# PCB_iter_3.net
KiCad netlist of a schematic drawn in EAGLE
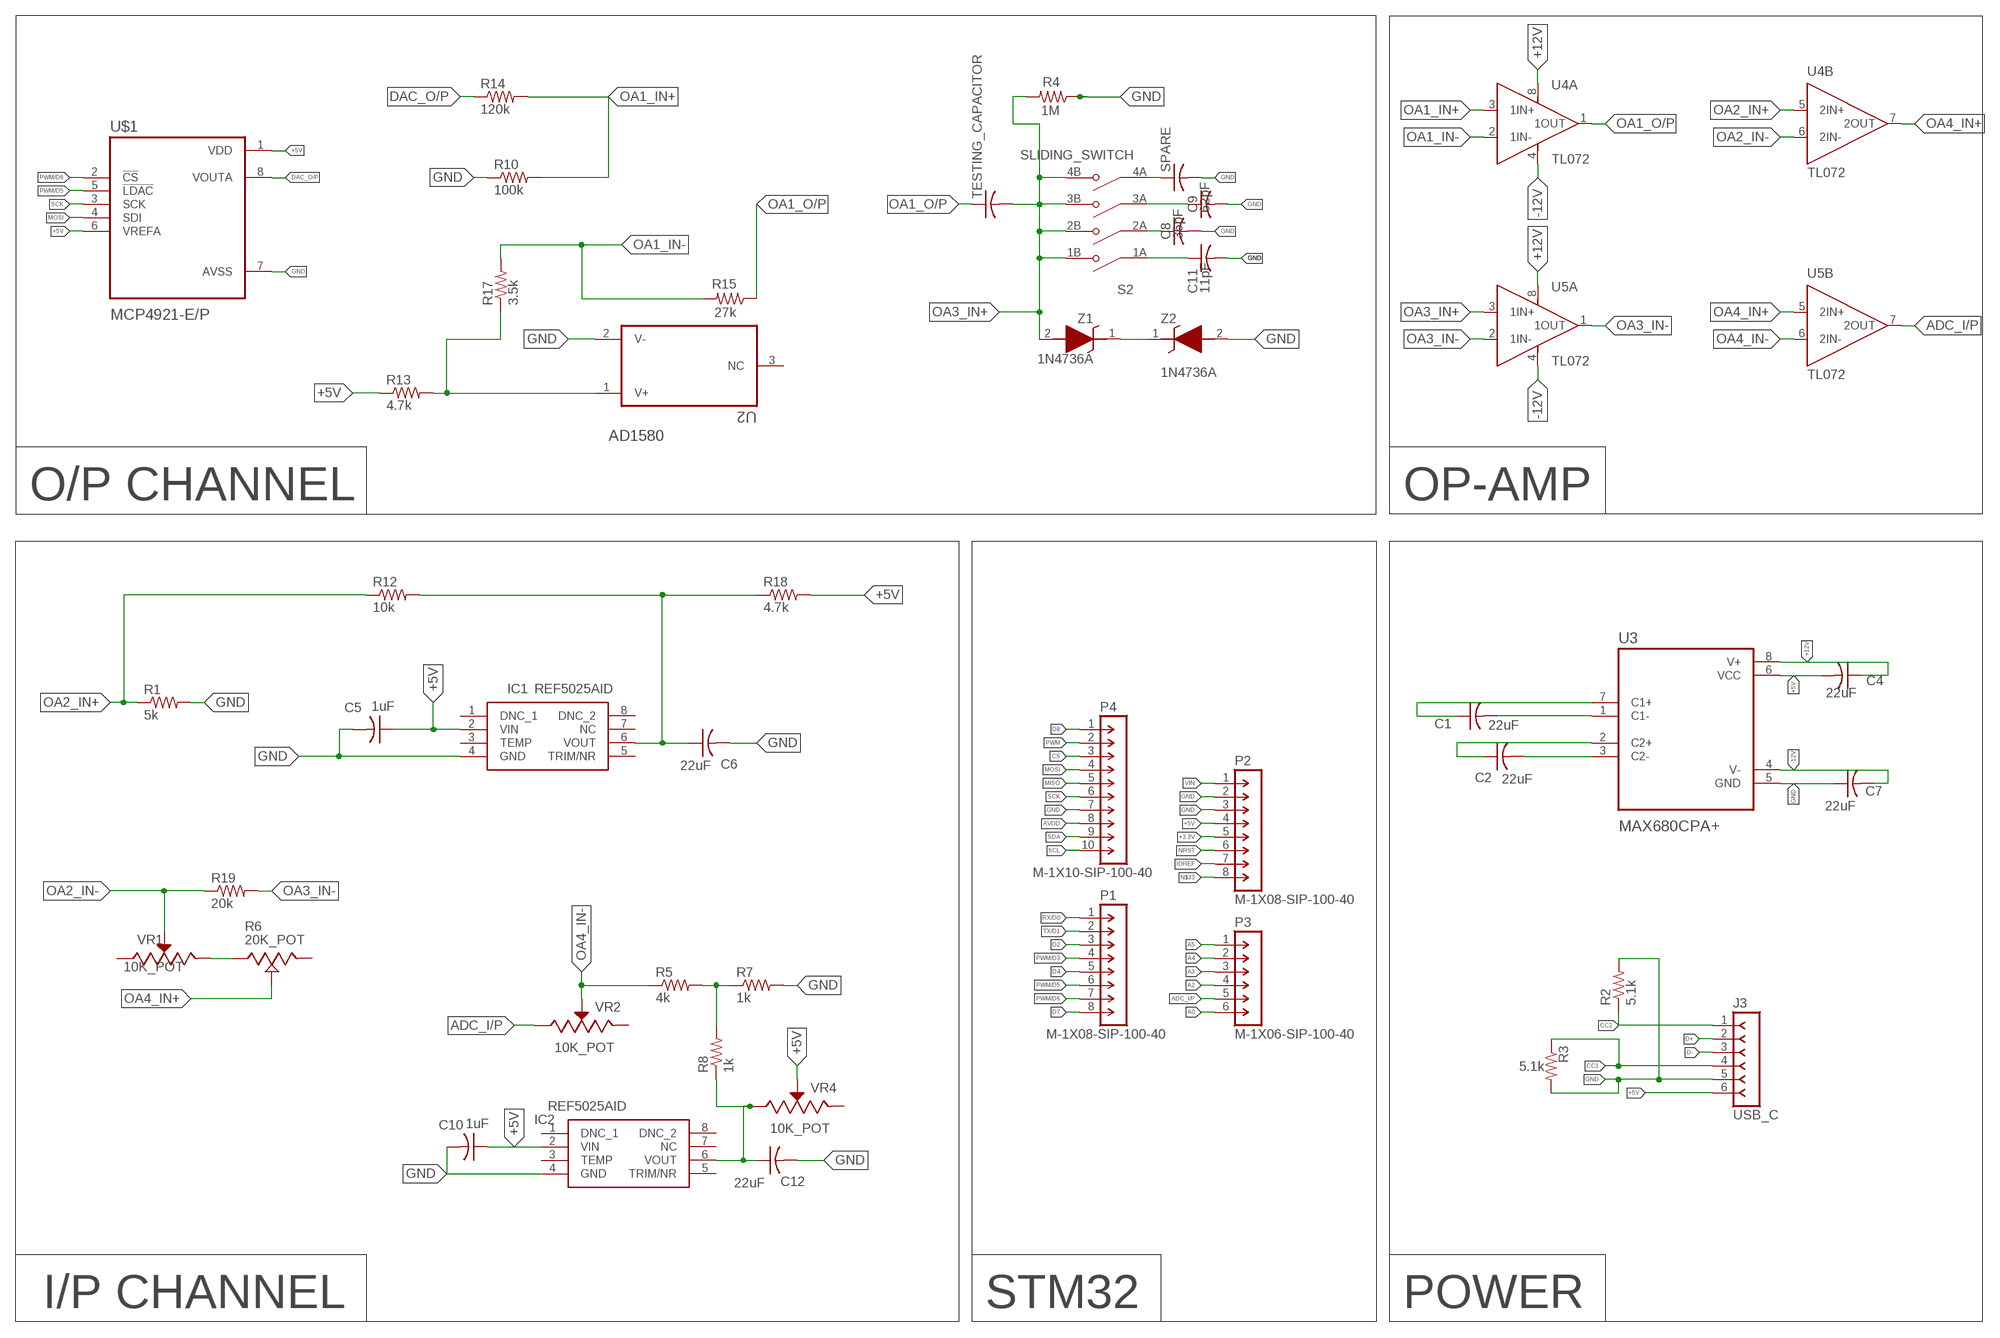
[diagram p0: schematic, sheet 1]

(export (version "E")
  (design (tool "Eeschema 10.0.6"))
  (components
    (comp (ref "C1")
      (value "22uF")
      (footprint "eagle-import:C1206")
      (libsource (lib "eagle-import") (part "C-USC1206"))
    )
    (comp (ref "C2")
      (value "22uF")
      (footprint "eagle-import:C1206")
      (libsource (lib "eagle-import") (part "C-USC1206"))
    )
    (comp (ref "C4")
      (value "22uF")
      (footprint "eagle-import:C1206")
      (libsource (lib "eagle-import") (part "C-USC1206"))
    )
    (comp (ref "C5")
      (value "1uF")
      (footprint "eagle-import:C1206")
      (libsource (lib "eagle-import") (part "C-USC1206"))
    )
    (comp (ref "C6")
      (value "22uF")
      (footprint "eagle-import:C1206")
      (libsource (lib "eagle-import") (part "C-USC1206"))
    )
    (comp (ref "C7")
      (value "22uF")
      (footprint "eagle-import:C1206")
      (libsource (lib "eagle-import") (part "C-USC1206"))
    )
    (comp (ref "C8")
      (value "36pF")
      (footprint "eagle-import:C1206")
      (libsource (lib "eagle-import") (part "C-USC1206"))
    )
    (comp (ref "C9")
      (value "62pF")
      (footprint "eagle-import:C1206")
      (libsource (lib "eagle-import") (part "C-USC1206"))
    )
    (comp (ref "C10")
      (value "1uF")
      (footprint "eagle-import:C1206")
      (libsource (lib "eagle-import") (part "C-USC1206"))
    )
    (comp (ref "C11")
      (value "11pF")
      (footprint "eagle-import:C1206")
      (fields (field (name "SPICEPREFIX") "C"))
      (libsource (lib "eagle-import") (part "C-USC1206"))
    )
    (comp (ref "C12")
      (value "22uF")
      (footprint "eagle-import:C1206")
      (libsource (lib "eagle-import") (part "C-USC1206"))
    )
    (comp (ref "IC1")
      (value "REF5025AID")
      (footprint "eagle-import:SOIC127P600X175-8N")
      (fields (field (name "MOUSER_PART_NUMBER") "595-REF5025AID"))
      (libsource (lib "eagle-import") (part "REF5025AID"))
    )
    (comp (ref "IC2")
      (value "REF5025AID")
      (footprint "eagle-import:SOIC127P600X175-8N")
      (fields (field (name "MOUSER_PART_NUMBER") "595-REF5025AID"))
      (libsource (lib "eagle-import") (part "REF5025AID"))
    )
    (comp (ref "J3")
      (value "USB_C")
      (footprint "eagle-import:SIP-100-06-40Y")
      (libsource (lib "eagle-import") (part "F-1X06-SIP-100-40Y"))
    )
    (comp (ref "P1")
      (value "M-1X08-SIP-100-40")
      (footprint "eagle-import:SIP-100-08-40")
      (libsource (lib "eagle-import") (part "M-1X08-SIP-100-40"))
    )
    (comp (ref "P2")
      (value "M-1X08-SIP-100-40")
      (footprint "eagle-import:SIP-100-08-40")
      (libsource (lib "eagle-import") (part "M-1X08-SIP-100-40"))
    )
    (comp (ref "P3")
      (value "M-1X06-SIP-100-40")
      (footprint "eagle-import:SIP-100-06-40")
      (libsource (lib "eagle-import") (part "M-1X06-SIP-100-40"))
    )
    (comp (ref "P4")
      (value "M-1X10-SIP-100-40")
      (footprint "eagle-import:SIP-100-10-40")
      (libsource (lib "eagle-import") (part "M-1X10-SIP-100-40"))
    )
    (comp (ref "R1")
      (value "5k")
      (footprint "eagle-import:M1206")
      (libsource (lib "eagle-import") (part "R-US_M1206"))
    )
    (comp (ref "R2")
      (value "5.1k")
      (footprint "eagle-import:R1206")
      (libsource (lib "eagle-import") (part "R-US_R1206"))
    )
    (comp (ref "R3")
      (value "5.1k")
      (footprint "eagle-import:R1206")
      (libsource (lib "eagle-import") (part "R-US_R1206"))
    )
    (comp (ref "R4")
      (value "1M")
      (footprint "eagle-import:M1206")
      (libsource (lib "eagle-import") (part "R-US_M1206"))
    )
    (comp (ref "R5")
      (value "4k")
      (footprint "eagle-import:M1206")
      (libsource (lib "eagle-import") (part "R-US_M1206"))
    )
    (comp (ref "R6")
      (value "20K_POT")
      (footprint "eagle-import:TRIM_3296X-1-203LF")
      (fields (field (name "MF") "Bourns") (field (name "MP") "3296X-1-203LF"))
      (libsource (lib "eagle-import") (part "3296X-1-203LF"))
    )
    (comp (ref "R7")
      (value "1k")
      (footprint "eagle-import:M1206")
      (libsource (lib "eagle-import") (part "R-US_M1206"))
    )
    (comp (ref "R8")
      (value "1k")
      (footprint "eagle-import:M1206")
      (libsource (lib "eagle-import") (part "R-US_M1206"))
    )
    (comp (ref "R10")
      (value "100k")
      (footprint "eagle-import:M1206")
      (libsource (lib "eagle-import") (part "R-US_M1206"))
    )
    (comp (ref "R12")
      (value "10k")
      (footprint "eagle-import:M1206")
      (libsource (lib "eagle-import") (part "R-US_M1206"))
    )
    (comp (ref "R13")
      (value "4.7k")
      (footprint "eagle-import:M1206")
      (libsource (lib "eagle-import") (part "R-US_M1206"))
    )
    (comp (ref "R14")
      (value "120k")
      (footprint "eagle-import:M1206")
      (libsource (lib "eagle-import") (part "R-US_M1206"))
    )
    (comp (ref "R15")
      (value "27k")
      (footprint "eagle-import:M1206")
      (libsource (lib "eagle-import") (part "R-US_M1206"))
    )
    (comp (ref "R17")
      (value "3.5k")
      (footprint "eagle-import:M1206")
      (libsource (lib "eagle-import") (part "R-US_M1206"))
    )
    (comp (ref "R18")
      (value "4.7k")
      (footprint "eagle-import:M1206")
      (libsource (lib "eagle-import") (part "R-US_M1206"))
    )
    (comp (ref "R19")
      (value "20k")
      (footprint "eagle-import:M1206")
      (libsource (lib "eagle-import") (part "R-US_M1206"))
    )
    (comp (ref "S2")
      (value "SLIDING_SWITCH")
      (footprint "eagle-import:SW_DS01C-254-S-04BE")
      (fields (field (name "MANUFACTURER") "CUI"))
      (libsource (lib "eagle-import") (part "DS01C-254-S-04BE"))
    )
    (comp (ref "SPARE")
      (value "C-USC1206")
      (footprint "eagle-import:C1206")
      (libsource (lib "eagle-import") (part "C-USC1206"))
    )
    (comp (ref "TESTING_CAPACITOR")
      (value "C-US050-030X075")
      (footprint "eagle-import:C050-030X075")
      (libsource (lib "eagle-import") (part "C-US050-030X075"))
    )
    (comp (ref "U$1")
      (value "MCP4921-E/P")
      (footprint "eagle-import:DIP787W46P254L927H533Q8")
      (fields (field (name "MF") "Microchip"))
      (libsource (lib "eagle-import") (part "MCP4921-E/P"))
    )
    (comp (ref "U2")
      (value "AD1580")
      (footprint "eagle-import:SOT96P237X112-3N")
      (libsource (lib "eagle-import") (part "AD1580BRTZ-R2-REEL7"))
    )
    (comp (ref "U3")
      (value "MAX680CPA+")
      (footprint "eagle-import:DIP794W47P254L991H457Q8")
      (fields (field (name "MF") "Maxim Integrated Products"))
      (libsource (lib "eagle-import") (part "MAX680CPA+"))
    )
    (comp (ref "U4")
      (value "TL072")
      (footprint "eagle-import:DIP794W45P254L1060H508Q8")
      (fields (field (name "MF") "Texas Instruments"))
      (libsource (lib "eagle-import") (part "TL072"))
    )
    (comp (ref "U5")
      (value "TL072")
      (footprint "eagle-import:DIP794W45P254L1060H508Q8")
      (fields (field (name "MF") "Texas Instruments"))
      (libsource (lib "eagle-import") (part "TL072"))
    )
    (comp (ref "VR1")
      (value "10K_POT")
      (footprint "eagle-import:TRIM_3296W-1-103RLF")
      (fields (field (name "MF") "Bourns") (field (name "MP") "3296W-1-103RLF"))
      (libsource (lib "eagle-import") (part "3296W-1-103RLF"))
    )
    (comp (ref "VR2")
      (value "10K_POT")
      (footprint "eagle-import:TRIM_3296W-1-103RLF")
      (fields (field (name "MF") "Bourns") (field (name "MP") "3296W-1-103RLF"))
      (libsource (lib "eagle-import") (part "3296W-1-103RLF"))
    )
    (comp (ref "VR4")
      (value "10K_POT")
      (footprint "eagle-import:TRIM_3296W-1-103RLF")
      (fields (field (name "MF") "Bourns") (field (name "MP") "3296W-1-103RLF"))
      (libsource (lib "eagle-import") (part "3296W-1-103RLF"))
    )
    (comp (ref "Z1")
      (value "1N4736A")
      (footprint "eagle-import:DIOAD1413W86L463D238")
      (fields (field (name "MOUSER_PART_NUMBER") "512-1N4736A"))
      (libsource (lib "eagle-import") (part "1N4736A"))
    )
    (comp (ref "Z2")
      (value "1N4736A")
      (footprint "eagle-import:DIOAD1413W86L463D238")
      (fields (field (name "MOUSER_PART_NUMBER") "512-1N4736A"))
      (libsource (lib "eagle-import") (part "1N4736A"))
    )
  )
  (nets
    (net (code "1") (name "+3.3V") (class "Default")
      (node (ref "P2") (pin "5") (pinfunction "5_5") (pintype "passive"))
    )
    (net (code "2") (name "+5V") (class "Default")
      (node (ref "C10") (pin "1") (pinfunction "1_1") (pintype "passive"))
      (node (ref "C4") (pin "2") (pinfunction "2_2") (pintype "passive"))
      (node (ref "C5") (pin "1") (pinfunction "1_1") (pintype "passive"))
      (node (ref "IC1") (pin "2") (pinfunction "VIN_2") (pintype "bidirectional"))
      (node (ref "IC2") (pin "2") (pinfunction "VIN_2") (pintype "bidirectional"))
      (node (ref "J3") (pin "6") (pinfunction "6_6") (pintype "passive"))
      (node (ref "P2") (pin "4") (pinfunction "4_4") (pintype "passive"))
      (node (ref "R13") (pin "1") (pinfunction "1_1") (pintype "passive"))
      (node (ref "R18") (pin "2") (pinfunction "2_2") (pintype "passive"))
      (node (ref "U$1") (pin "1") (pinfunction "VDD_1") (pintype "power_in"))
      (node (ref "U$1") (pin "6") (pinfunction "VREFA_6") (pintype "input"))
      (node (ref "U3") (pin "6") (pinfunction "VCC_6") (pintype "power_in"))
      (node (ref "VR4") (pin "2") (pinfunction "WIPER_2") (pintype "passive"))
    )
    (net (code "3") (name "+12V") (class "Default")
      (node (ref "C4") (pin "1") (pinfunction "1_1") (pintype "passive"))
      (node (ref "U3") (pin "8") (pinfunction "V+_8") (pintype "power_in"))
      (node (ref "U4") (pin "8") (pinfunction "VCC+_8") (pintype "power_in"))
      (node (ref "U5") (pin "8") (pinfunction "VCC+_8") (pintype "power_in"))
    )
    (net (code "4") (name "-12V") (class "Default")
      (node (ref "C7") (pin "2") (pinfunction "2_2") (pintype "passive"))
      (node (ref "U3") (pin "4") (pinfunction "V-_4") (pintype "power_in"))
      (node (ref "U4") (pin "4") (pinfunction "VCC-_4") (pintype "power_in"))
      (node (ref "U5") (pin "4") (pinfunction "VCC-_4") (pintype "power_in"))
    )
    (net (code "5") (name "A0") (class "Default")
      (node (ref "P3") (pin "6") (pinfunction "6_6") (pintype "passive"))
    )
    (net (code "6") (name "A2") (class "Default")
      (node (ref "P3") (pin "4") (pinfunction "4_4") (pintype "passive"))
    )
    (net (code "7") (name "A3") (class "Default")
      (node (ref "P3") (pin "3") (pinfunction "3_3") (pintype "passive"))
    )
    (net (code "8") (name "A4") (class "Default")
      (node (ref "P3") (pin "2") (pinfunction "2_2") (pintype "passive"))
    )
    (net (code "9") (name "A5") (class "Default")
      (node (ref "P3") (pin "1") (pinfunction "1_1") (pintype "passive"))
    )
    (net (code "10") (name "ADC_I{slash}P") (class "Default")
      (node (ref "P3") (pin "5") (pinfunction "5_5") (pintype "passive"))
      (node (ref "U5") (pin "7") (pinfunction "2OUT_7") (pintype "output"))
      (node (ref "VR2") (pin "1") (pinfunction "CCW_1") (pintype "passive"))
    )
    (net (code "11") (name "AVDD") (class "Default")
      (node (ref "P4") (pin "8") (pinfunction "8_8") (pintype "passive"))
    )
    (net (code "12") (name "CC1") (class "Default")
      (node (ref "J3") (pin "4") (pinfunction "4_4") (pintype "passive"))
      (node (ref "R3") (pin "1") (pinfunction "1_1") (pintype "passive"))
    )
    (net (code "13") (name "CC2") (class "Default")
      (node (ref "J3") (pin "1") (pinfunction "1_1") (pintype "passive"))
      (node (ref "R2") (pin "1") (pinfunction "1_1") (pintype "passive"))
    )
    (net (code "14") (name "CS") (class "Default")
      (node (ref "P4") (pin "3") (pinfunction "3_3") (pintype "passive"))
    )
    (net (code "15") (name "D+") (class "Default")
      (node (ref "J3") (pin "2") (pinfunction "2_2") (pintype "passive"))
    )
    (net (code "16") (name "D-") (class "Default")
      (node (ref "J3") (pin "3") (pinfunction "3_3") (pintype "passive"))
    )
    (net (code "17") (name "D2") (class "Default")
      (node (ref "P1") (pin "3") (pinfunction "3_3") (pintype "passive"))
    )
    (net (code "18") (name "D4") (class "Default")
      (node (ref "P1") (pin "5") (pinfunction "5_5") (pintype "passive"))
    )
    (net (code "19") (name "D7") (class "Default")
      (node (ref "P1") (pin "8") (pinfunction "8_8") (pintype "passive"))
    )
    (net (code "20") (name "D8") (class "Default")
      (node (ref "P4") (pin "1") (pinfunction "1_1") (pintype "passive"))
    )
    (net (code "21") (name "DAC_O{slash}P") (class "Default")
      (node (ref "R14") (pin "1") (pinfunction "1_1") (pintype "passive"))
      (node (ref "U$1") (pin "8") (pinfunction "VOUTA_8") (pintype "output"))
    )
    (net (code "22") (name "GND") (class "Default")
      (node (ref "C10") (pin "2") (pinfunction "2_2") (pintype "passive"))
      (node (ref "C11") (pin "2") (pinfunction "2_2") (pintype "passive"))
      (node (ref "C12") (pin "2") (pinfunction "2_2") (pintype "passive"))
      (node (ref "C5") (pin "2") (pinfunction "2_2") (pintype "passive"))
      (node (ref "C6") (pin "2") (pinfunction "2_2") (pintype "passive"))
      (node (ref "C7") (pin "1") (pinfunction "1_1") (pintype "passive"))
      (node (ref "C8") (pin "2") (pinfunction "2_2") (pintype "passive"))
      (node (ref "C9") (pin "2") (pinfunction "2_2") (pintype "passive"))
      (node (ref "IC1") (pin "4") (pinfunction "GND_4") (pintype "bidirectional"))
      (node (ref "IC2") (pin "4") (pinfunction "GND_4") (pintype "bidirectional"))
      (node (ref "J3") (pin "5") (pinfunction "5_5") (pintype "passive"))
      (node (ref "P2") (pin "2") (pinfunction "2_2") (pintype "passive"))
      (node (ref "P2") (pin "3") (pinfunction "3_3") (pintype "passive"))
      (node (ref "P4") (pin "7") (pinfunction "7_7") (pintype "passive"))
      (node (ref "R1") (pin "2") (pinfunction "2_2") (pintype "passive"))
      (node (ref "R10") (pin "1") (pinfunction "1_1") (pintype "passive"))
      (node (ref "R2") (pin "2") (pinfunction "2_2") (pintype "passive"))
      (node (ref "R3") (pin "2") (pinfunction "2_2") (pintype "passive"))
      (node (ref "R4") (pin "1") (pinfunction "1_1") (pintype "passive"))
      (node (ref "R7") (pin "2") (pinfunction "2_2") (pintype "passive"))
      (node (ref "SPARE") (pin "2") (pinfunction "2_2") (pintype "passive"))
      (node (ref "U$1") (pin "7") (pinfunction "AVSS_7") (pintype "power_in"))
      (node (ref "U2") (pin "2") (pinfunction "V-_2") (pintype "power_in"))
      (node (ref "U3") (pin "5") (pinfunction "GND_5") (pintype "power_in"))
      (node (ref "Z2") (pin "2") (pinfunction "A_2") (pintype "bidirectional"))
    )
    (net (code "23") (name "IOREF") (class "Default")
      (node (ref "P2") (pin "7") (pinfunction "7_7") (pintype "passive"))
    )
    (net (code "24") (name "MISO") (class "Default")
      (node (ref "P4") (pin "5") (pinfunction "5_5") (pintype "passive"))
    )
    (net (code "25") (name "MOSI") (class "Default")
      (node (ref "P4") (pin "4") (pinfunction "4_4") (pintype "passive"))
      (node (ref "U$1") (pin "4") (pinfunction "SDI_4") (pintype "input"))
    )
    (net (code "26") (name "N$33") (class "Default")
      (node (ref "P2") (pin "8") (pinfunction "8_8") (pintype "passive"))
    )
    (net (code "27") (name "NRST") (class "Default")
      (node (ref "P2") (pin "6") (pinfunction "6_6") (pintype "passive"))
    )
    (net (code "28") (name "Net-(IC1-VOUT)") (class "Default")
      (node (ref "C6") (pin "1") (pinfunction "1_1") (pintype "passive"))
      (node (ref "IC1") (pin "6") (pinfunction "VOUT_6") (pintype "bidirectional"))
      (node (ref "R12") (pin "2") (pinfunction "2_2") (pintype "passive"))
      (node (ref "R18") (pin "1") (pinfunction "1_1") (pintype "passive"))
    )
    (net (code "29") (name "Net-(IC2-VOUT)") (class "Default")
      (node (ref "C12") (pin "1") (pinfunction "1_1") (pintype "passive"))
      (node (ref "IC2") (pin "6") (pinfunction "VOUT_6") (pintype "bidirectional"))
      (node (ref "R8") (pin "1") (pinfunction "1_1") (pintype "passive"))
      (node (ref "VR4") (pin "1") (pinfunction "CCW_1") (pintype "passive"))
    )
    (net (code "30") (name "Net-(R5-Pad2)") (class "Default")
      (node (ref "R5") (pin "2") (pinfunction "2_2") (pintype "passive"))
      (node (ref "R7") (pin "1") (pinfunction "1_1") (pintype "passive"))
      (node (ref "R8") (pin "2") (pinfunction "2_2") (pintype "passive"))
    )
    (net (code "31") (name "Net-(R6-CCW)") (class "Default")
      (node (ref "R6") (pin "1") (pinfunction "CCW_1") (pintype "passive"))
      (node (ref "VR1") (pin "3") (pinfunction "CW_3") (pintype "passive"))
    )
    (net (code "32") (name "Net-(S2-COM1)") (class "Default")
      (node (ref "C11") (pin "1") (pinfunction "1_1") (pintype "passive"))
      (node (ref "S2") (pin "1A") (pinfunction "COM1_1A") (pintype "passive"))
    )
    (net (code "33") (name "Net-(S2-COM2)") (class "Default")
      (node (ref "C8") (pin "1") (pinfunction "1_1") (pintype "passive"))
      (node (ref "S2") (pin "2A") (pinfunction "COM2_2A") (pintype "passive"))
    )
    (net (code "34") (name "Net-(S2-COM3)") (class "Default")
      (node (ref "C9") (pin "1") (pinfunction "1_1") (pintype "passive"))
      (node (ref "S2") (pin "3A") (pinfunction "COM3_3A") (pintype "passive"))
    )
    (net (code "35") (name "Net-(S2-COM4)") (class "Default")
      (node (ref "S2") (pin "4A") (pinfunction "COM4_4A") (pintype "passive"))
      (node (ref "SPARE") (pin "1") (pinfunction "1_1") (pintype "passive"))
    )
    (net (code "36") (name "Net-(U2-V+)") (class "Default")
      (node (ref "R13") (pin "2") (pinfunction "2_2") (pintype "passive"))
      (node (ref "R17") (pin "1") (pinfunction "1_1") (pintype "passive"))
      (node (ref "U2") (pin "1") (pinfunction "V+_1") (pintype "power_in"))
    )
    (net (code "37") (name "Net-(U3-C1+)") (class "Default")
      (node (ref "C1") (pin "1") (pinfunction "1_1") (pintype "passive"))
      (node (ref "U3") (pin "7") (pinfunction "C1+_7") (pintype "passive"))
    )
    (net (code "38") (name "Net-(U3-C1-)") (class "Default")
      (node (ref "C1") (pin "2") (pinfunction "2_2") (pintype "passive"))
      (node (ref "U3") (pin "1") (pinfunction "C1-_1") (pintype "passive"))
    )
    (net (code "39") (name "Net-(U3-C2+)") (class "Default")
      (node (ref "C2") (pin "1") (pinfunction "1_1") (pintype "passive"))
      (node (ref "U3") (pin "2") (pinfunction "C2+_2") (pintype "passive"))
    )
    (net (code "40") (name "Net-(U3-C2-)") (class "Default")
      (node (ref "C2") (pin "2") (pinfunction "2_2") (pintype "passive"))
      (node (ref "U3") (pin "3") (pinfunction "C2-_3") (pintype "passive"))
    )
    (net (code "41") (name "Net-(Z1-K)") (class "Default")
      (node (ref "Z1") (pin "1") (pinfunction "K_1") (pintype "bidirectional"))
      (node (ref "Z2") (pin "1") (pinfunction "K_1") (pintype "bidirectional"))
    )
    (net (code "42") (name "OA1_IN+") (class "Default")
      (node (ref "R10") (pin "2") (pinfunction "2_2") (pintype "passive"))
      (node (ref "R14") (pin "2") (pinfunction "2_2") (pintype "passive"))
      (node (ref "U4") (pin "3") (pinfunction "1IN+_3") (pintype "input"))
    )
    (net (code "43") (name "OA1_IN-") (class "Default")
      (node (ref "R15") (pin "2") (pinfunction "2_2") (pintype "passive"))
      (node (ref "R17") (pin "2") (pinfunction "2_2") (pintype "passive"))
      (node (ref "U4") (pin "2") (pinfunction "1IN-_2") (pintype "input"))
    )
    (net (code "44") (name "OA1_O{slash}P") (class "Default")
      (node (ref "R15") (pin "1") (pinfunction "1_1") (pintype "passive"))
      (node (ref "TESTING_CAPACITOR") (pin "1") (pinfunction "1_1") (pintype "passive"))
      (node (ref "U4") (pin "1") (pinfunction "1OUT_1") (pintype "output"))
    )
    (net (code "45") (name "OA2_IN+") (class "Default")
      (node (ref "R1") (pin "1") (pinfunction "1_1") (pintype "passive"))
      (node (ref "R12") (pin "1") (pinfunction "1_1") (pintype "passive"))
      (node (ref "U4") (pin "5") (pinfunction "2IN+_5") (pintype "input"))
    )
    (net (code "46") (name "OA2_IN-") (class "Default")
      (node (ref "R19") (pin "1") (pinfunction "1_1") (pintype "passive"))
      (node (ref "U4") (pin "6") (pinfunction "2IN-_6") (pintype "input"))
      (node (ref "VR1") (pin "2") (pinfunction "WIPER_2") (pintype "passive"))
    )
    (net (code "47") (name "OA3_IN+") (class "Default")
      (node (ref "R4") (pin "2") (pinfunction "2_2") (pintype "passive"))
      (node (ref "S2") (pin "1B") (pinfunction "NO1_1B") (pintype "passive"))
      (node (ref "S2") (pin "2B") (pinfunction "NO2_2B") (pintype "passive"))
      (node (ref "S2") (pin "3B") (pinfunction "NO3_3B") (pintype "passive"))
      (node (ref "S2") (pin "4B") (pinfunction "NO4_4B") (pintype "passive"))
      (node (ref "TESTING_CAPACITOR") (pin "2") (pinfunction "2_2") (pintype "passive"))
      (node (ref "U5") (pin "3") (pinfunction "1IN+_3") (pintype "input"))
      (node (ref "Z1") (pin "2") (pinfunction "A_2") (pintype "bidirectional"))
    )
    (net (code "48") (name "OA3_IN-") (class "Default")
      (node (ref "R19") (pin "2") (pinfunction "2_2") (pintype "passive"))
      (node (ref "U5") (pin "1") (pinfunction "1OUT_1") (pintype "output"))
      (node (ref "U5") (pin "2") (pinfunction "1IN-_2") (pintype "input"))
    )
    (net (code "49") (name "OA4_IN+") (class "Default")
      (node (ref "R6") (pin "2") (pinfunction "WIPER_2") (pintype "passive"))
      (node (ref "U4") (pin "7") (pinfunction "2OUT_7") (pintype "output"))
      (node (ref "U5") (pin "5") (pinfunction "2IN+_5") (pintype "input"))
    )
    (net (code "50") (name "OA4_IN-") (class "Default")
      (node (ref "R5") (pin "1") (pinfunction "1_1") (pintype "passive"))
      (node (ref "U5") (pin "6") (pinfunction "2IN-_6") (pintype "input"))
      (node (ref "VR2") (pin "2") (pinfunction "WIPER_2") (pintype "passive"))
    )
    (net (code "51") (name "PWM") (class "Default")
      (node (ref "P4") (pin "2") (pinfunction "2_2") (pintype "passive"))
    )
    (net (code "52") (name "PWM{slash}D3") (class "Default")
      (node (ref "P1") (pin "4") (pinfunction "4_4") (pintype "passive"))
    )
    (net (code "53") (name "PWM{slash}D5") (class "Default")
      (node (ref "P1") (pin "6") (pinfunction "6_6") (pintype "passive"))
      (node (ref "U$1") (pin "5") (pinfunction "~{LDAC}_5") (pintype "input"))
    )
    (net (code "54") (name "PWM{slash}D6") (class "Default")
      (node (ref "P1") (pin "7") (pinfunction "7_7") (pintype "passive"))
      (node (ref "U$1") (pin "2") (pinfunction "~{CS}_2") (pintype "input"))
    )
    (net (code "55") (name "RX{slash}D0") (class "Default")
      (node (ref "P1") (pin "1") (pinfunction "1_1") (pintype "passive"))
    )
    (net (code "56") (name "SCK") (class "Default")
      (node (ref "P4") (pin "6") (pinfunction "6_6") (pintype "passive"))
      (node (ref "U$1") (pin "3") (pinfunction "SCK_3") (pintype "input"))
    )
    (net (code "57") (name "SCL") (class "Default")
      (node (ref "P4") (pin "10") (pinfunction "10_10") (pintype "passive"))
    )
    (net (code "58") (name "SDA") (class "Default")
      (node (ref "P4") (pin "9") (pinfunction "9_9") (pintype "passive"))
    )
    (net (code "59") (name "TX{slash}D1") (class "Default")
      (node (ref "P1") (pin "2") (pinfunction "2_2") (pintype "passive"))
    )
    (net (code "60") (name "VIN") (class "Default")
      (node (ref "P2") (pin "1") (pinfunction "1_1") (pintype "passive"))
    )
    (net (code "61") (name "unconnected-(IC1-DNC_1-Pad1)") (class "Default")
      (node (ref "IC1") (pin "1") (pinfunction "DNC_1_1") (pintype "bidirectional"))
    )
    (net (code "62") (name "unconnected-(IC1-DNC_2-Pad8)") (class "Default")
      (node (ref "IC1") (pin "8") (pinfunction "DNC_2_8") (pintype "bidirectional"))
    )
    (net (code "63") (name "unconnected-(IC1-NC-Pad7)") (class "Default")
      (node (ref "IC1") (pin "7") (pinfunction "NC_7") (pintype "no_connect"))
    )
    (net (code "64") (name "unconnected-(IC1-TEMP-Pad3)") (class "Default")
      (node (ref "IC1") (pin "3") (pinfunction "TEMP_3") (pintype "bidirectional"))
    )
    (net (code "65") (name "unconnected-(IC1-TRIM{slash}NR-Pad5)") (class "Default")
      (node (ref "IC1") (pin "5") (pinfunction "TRIM/NR_5") (pintype "bidirectional"))
    )
    (net (code "66") (name "unconnected-(IC2-DNC_1-Pad1)") (class "Default")
      (node (ref "IC2") (pin "1") (pinfunction "DNC_1_1") (pintype "bidirectional"))
    )
    (net (code "67") (name "unconnected-(IC2-DNC_2-Pad8)") (class "Default")
      (node (ref "IC2") (pin "8") (pinfunction "DNC_2_8") (pintype "bidirectional"))
    )
    (net (code "68") (name "unconnected-(IC2-NC-Pad7)") (class "Default")
      (node (ref "IC2") (pin "7") (pinfunction "NC_7") (pintype "no_connect"))
    )
    (net (code "69") (name "unconnected-(IC2-TEMP-Pad3)") (class "Default")
      (node (ref "IC2") (pin "3") (pinfunction "TEMP_3") (pintype "bidirectional"))
    )
    (net (code "70") (name "unconnected-(IC2-TRIM{slash}NR-Pad5)") (class "Default")
      (node (ref "IC2") (pin "5") (pinfunction "TRIM/NR_5") (pintype "bidirectional"))
    )
    (net (code "71") (name "unconnected-(R6-CW-Pad3)") (class "Default")
      (node (ref "R6") (pin "3") (pinfunction "CW_3") (pintype "passive"))
    )
    (net (code "72") (name "unconnected-(U2-NC-Pad3)") (class "Default")
      (node (ref "U2") (pin "3") (pinfunction "NC_3") (pintype "bidirectional"))
    )
    (net (code "73") (name "unconnected-(VR1-CCW-Pad1)") (class "Default")
      (node (ref "VR1") (pin "1") (pinfunction "CCW_1") (pintype "passive"))
    )
    (net (code "74") (name "unconnected-(VR2-CW-Pad3)") (class "Default")
      (node (ref "VR2") (pin "3") (pinfunction "CW_3") (pintype "passive"))
    )
    (net (code "75") (name "unconnected-(VR4-CW-Pad3)") (class "Default")
      (node (ref "VR4") (pin "3") (pinfunction "CW_3") (pintype "passive"))
    )
  )
)
